# codec_AD1938.net
KiCad netlist of a schematic drawn in EAGLE
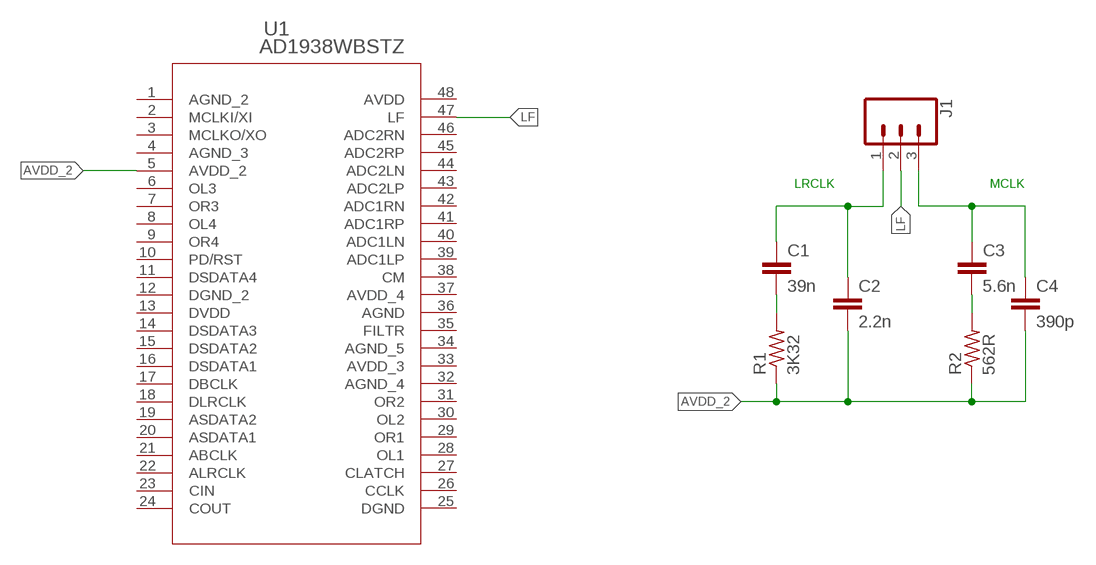
[diagram p0: schematic, sheet 1]
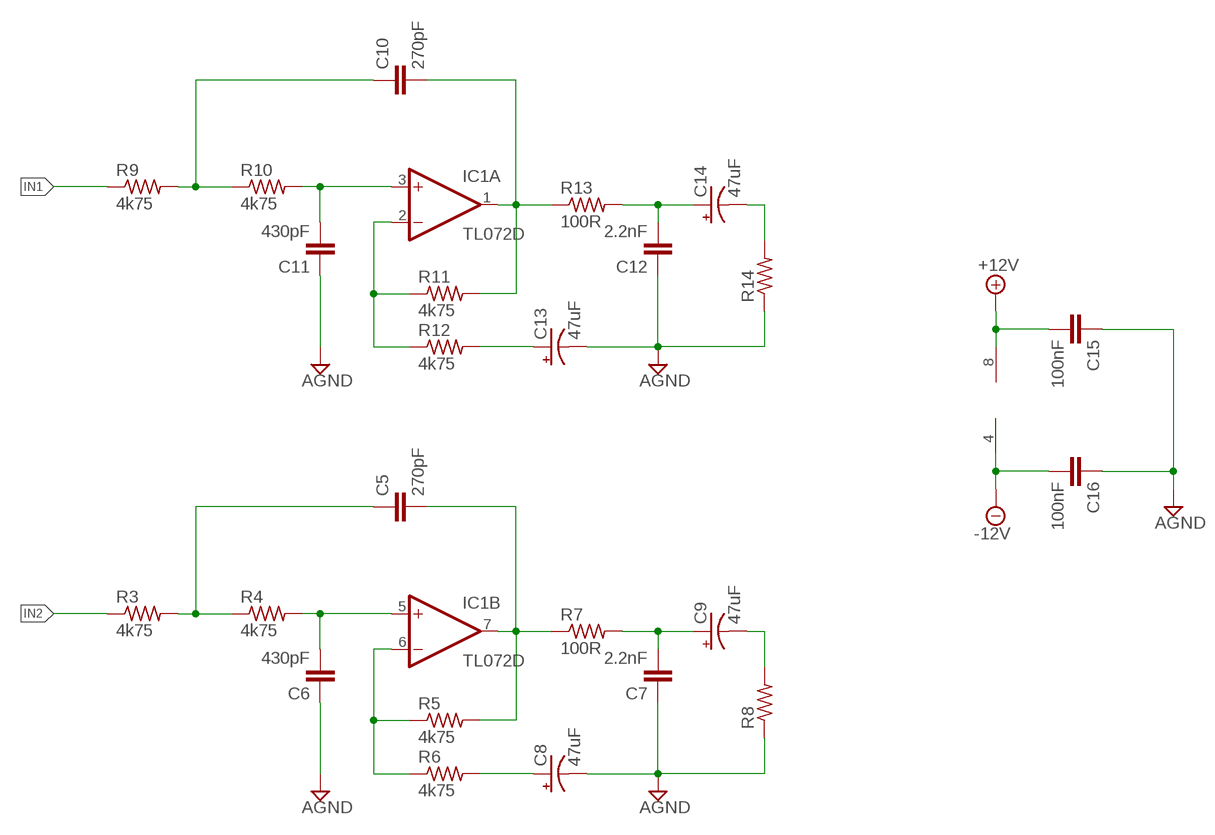
[diagram p1: schematic, sheet 2]

(export (version "E")
  (design (tool "Eeschema 10.0.6"))
  (components
    (comp (ref "C5")
      (value "270pF")
      (footprint "eagle-import:C0603")
      (libsource (lib "eagle-import") (part "C-EUC0603"))
    )
    (comp (ref "C6")
      (value "430pF")
      (footprint "eagle-import:C0603")
      (libsource (lib "eagle-import") (part "C-EUC0603"))
    )
    (comp (ref "C7")
      (value "2.2nF")
      (footprint "eagle-import:C0603")
      (libsource (lib "eagle-import") (part "C-EUC0603"))
    )
    (comp (ref "C8")
      (value "47uF")
      (footprint "eagle-import:UD-5X5,8_NICHICON")
      (libsource (lib "eagle-import") (part "CPOL-USUD-5X5,8"))
    )
    (comp (ref "C9")
      (value "47uF")
      (footprint "eagle-import:UD-5X5,8_NICHICON")
      (libsource (lib "eagle-import") (part "CPOL-USUD-5X5,8"))
    )
    (comp (ref "C10")
      (value "270pF")
      (footprint "eagle-import:C0603")
      (libsource (lib "eagle-import") (part "C-EUC0603"))
    )
    (comp (ref "C11")
      (value "430pF")
      (footprint "eagle-import:C0603")
      (libsource (lib "eagle-import") (part "C-EUC0603"))
    )
    (comp (ref "C12")
      (value "2.2nF")
      (footprint "eagle-import:C0603")
      (libsource (lib "eagle-import") (part "C-EUC0603"))
    )
    (comp (ref "C13")
      (value "47uF")
      (footprint "eagle-import:UD-5X5,8_NICHICON")
      (libsource (lib "eagle-import") (part "CPOL-USUD-5X5,8"))
    )
    (comp (ref "C14")
      (value "47uF")
      (footprint "eagle-import:UD-5X5,8_NICHICON")
      (libsource (lib "eagle-import") (part "CPOL-USUD-5X5,8"))
    )
    (comp (ref "C15")
      (value "100nF")
      (footprint "eagle-import:C0603")
      (libsource (lib "eagle-import") (part "C-EUC0603"))
    )
    (comp (ref "C16")
      (value "100nF")
      (footprint "eagle-import:C0603")
      (libsource (lib "eagle-import") (part "C-EUC0603"))
    )
    (comp (ref "IC1")
      (value "TL072D")
      (footprint "eagle-import:SO08")
      (libsource (lib "eagle-import") (part "TL072D"))
    )
    (comp (ref "R3")
      (value "4k75")
      (footprint "eagle-import:R0603")
      (libsource (lib "eagle-import") (part "R-US_R0603"))
    )
    (comp (ref "R4")
      (value "4k75")
      (footprint "eagle-import:R0603")
      (libsource (lib "eagle-import") (part "R-US_R0603"))
    )
    (comp (ref "R5")
      (value "4k75")
      (footprint "eagle-import:R0603")
      (libsource (lib "eagle-import") (part "R-US_R0603"))
    )
    (comp (ref "R6")
      (value "4k75")
      (footprint "eagle-import:R0603")
      (libsource (lib "eagle-import") (part "R-US_R0603"))
    )
    (comp (ref "R7")
      (value "100R")
      (footprint "eagle-import:R0603")
      (libsource (lib "eagle-import") (part "R-US_R0603"))
    )
    (comp (ref "R8")
      (value "R-US_R0603")
      (footprint "eagle-import:R0603")
      (libsource (lib "eagle-import") (part "R-US_R0603"))
    )
    (comp (ref "R9")
      (value "4k75")
      (footprint "eagle-import:R0603")
      (libsource (lib "eagle-import") (part "R-US_R0603"))
    )
    (comp (ref "R10")
      (value "4k75")
      (footprint "eagle-import:R0603")
      (libsource (lib "eagle-import") (part "R-US_R0603"))
    )
    (comp (ref "R11")
      (value "4k75")
      (footprint "eagle-import:R0603")
      (libsource (lib "eagle-import") (part "R-US_R0603"))
    )
    (comp (ref "R12")
      (value "4k75")
      (footprint "eagle-import:R0603")
      (libsource (lib "eagle-import") (part "R-US_R0603"))
    )
    (comp (ref "R13")
      (value "100R")
      (footprint "eagle-import:R0603")
      (libsource (lib "eagle-import") (part "R-US_R0603"))
    )
    (comp (ref "R14")
      (value "R-US_R0603")
      (footprint "eagle-import:R0603")
      (libsource (lib "eagle-import") (part "R-US_R0603"))
    )
    (comp (ref "C1")
      (value "39n")
      (footprint "eagle-import:C0603")
      (libsource (lib "eagle-import") (part "C-EUC0603"))
    )
    (comp (ref "C2")
      (value "2.2n")
      (footprint "eagle-import:C0603")
      (libsource (lib "eagle-import") (part "C-EUC0603"))
    )
    (comp (ref "C3")
      (value "5.6n")
      (footprint "eagle-import:C0603")
      (libsource (lib "eagle-import") (part "C-EUC0603"))
    )
    (comp (ref "C4")
      (value "390p")
      (footprint "eagle-import:C0603")
      (libsource (lib "eagle-import") (part "C-EUC0603"))
    )
    (comp (ref "J1")
      (value "CONN_03LOCK_LONGPADS")
      (footprint "eagle-import:1X03_LOCK_LONGPADS")
      (libsource (lib "eagle-import") (part "CONN_03LOCK_LONGPADS"))
    )
    (comp (ref "R1")
      (value "3K32")
      (footprint "eagle-import:R0603")
      (libsource (lib "eagle-import") (part "R-US_R0603"))
    )
    (comp (ref "R2")
      (value "562R")
      (footprint "eagle-import:R0603")
      (libsource (lib "eagle-import") (part "R-US_R0603"))
    )
    (comp (ref "U1")
      (value "AD1938WBSTZ")
      (footprint "eagle-import:ST_48_ADI")
      (fields (field (name "COPYRIGHT") "Copyright (C) 2022 Ultra Librarian. All rights reserved."))
      (libsource (lib "eagle-import") (part "AD1938WBSTZ"))
    )
  )
  (nets
    (net (code "1") (name "+12V") (class "Default")
      (node (ref "C15") (pin "2") (pinfunction "2_2") (pintype "passive"))
      (node (ref "IC1") (pin "8") (pinfunction "V+_8") (pintype "power_in"))
    )
    (net (code "2") (name "-12V") (class "Default")
      (node (ref "C16") (pin "2") (pinfunction "2_2") (pintype "passive"))
      (node (ref "IC1") (pin "4") (pinfunction "V-_4") (pintype "power_in"))
    )
    (net (code "3") (name "AGND") (class "Default")
      (node (ref "C11") (pin "1") (pinfunction "1_1") (pintype "passive"))
      (node (ref "C12") (pin "1") (pinfunction "1_1") (pintype "passive"))
      (node (ref "C13") (pin "-") (pinfunction "-_-") (pintype "passive"))
      (node (ref "C15") (pin "1") (pinfunction "1_1") (pintype "passive"))
      (node (ref "C16") (pin "1") (pinfunction "1_1") (pintype "passive"))
      (node (ref "C6") (pin "1") (pinfunction "1_1") (pintype "passive"))
      (node (ref "C7") (pin "1") (pinfunction "1_1") (pintype "passive"))
      (node (ref "C8") (pin "-") (pinfunction "-_-") (pintype "passive"))
      (node (ref "R14") (pin "1") (pinfunction "1_1") (pintype "passive"))
      (node (ref "R8") (pin "1") (pinfunction "1_1") (pintype "passive"))
    )
    (net (code "4") (name "AVDD") (class "Default")
      (node (ref "U1") (pin "48") (pinfunction "AVDD_48") (pintype "power_in"))
    )
    (net (code "5") (name "AVDD_2") (class "Default")
      (node (ref "C2") (pin "2") (pinfunction "2_2") (pintype "passive"))
      (node (ref "C4") (pin "2") (pinfunction "2_2") (pintype "passive"))
      (node (ref "R1") (pin "1") (pinfunction "1_1") (pintype "passive"))
      (node (ref "R2") (pin "1") (pinfunction "1_1") (pintype "passive"))
      (node (ref "U1") (pin "5") (pinfunction "AVDD_2_5") (pintype "power_in"))
    )
    (net (code "6") (name "AVDD_3") (class "Default")
      (node (ref "U1") (pin "33") (pinfunction "AVDD_3_33") (pintype "power_in"))
    )
    (net (code "7") (name "AVDD_4") (class "Default")
      (node (ref "U1") (pin "37") (pinfunction "AVDD_4_37") (pintype "power_in"))
    )
    (net (code "8") (name "DVDD") (class "Default")
      (node (ref "U1") (pin "13") (pinfunction "DVDD_13") (pintype "power_in"))
    )
    (net (code "9") (name "IN1") (class "Default")
      (node (ref "R9") (pin "1") (pinfunction "1_1") (pintype "passive"))
    )
    (net (code "10") (name "IN2") (class "Default")
      (node (ref "R3") (pin "1") (pinfunction "1_1") (pintype "passive"))
    )
    (net (code "11") (name "LF") (class "Default")
      (node (ref "C1") (pin "1") (pinfunction "1_1") (pintype "passive"))
      (node (ref "C2") (pin "1") (pinfunction "1_1") (pintype "passive"))
      (node (ref "C3") (pin "1") (pinfunction "1_1") (pintype "passive"))
      (node (ref "C4") (pin "1") (pinfunction "1_1") (pintype "passive"))
      (node (ref "J1") (pin "1") (pinfunction "1_1") (pintype "passive"))
      (node (ref "J1") (pin "2") (pinfunction "2_2") (pintype "passive"))
      (node (ref "J1") (pin "3") (pinfunction "3_3") (pintype "passive"))
      (node (ref "U1") (pin "47") (pinfunction "LF_47") (pintype "passive"))
    )
    (net (code "12") (name "Net-(C1-Pad2)") (class "Default")
      (node (ref "C1") (pin "2") (pinfunction "2_2") (pintype "passive"))
      (node (ref "R1") (pin "2") (pinfunction "2_2") (pintype "passive"))
    )
    (net (code "13") (name "Net-(C3-Pad2)") (class "Default")
      (node (ref "C3") (pin "2") (pinfunction "2_2") (pintype "passive"))
      (node (ref "R2") (pin "2") (pinfunction "2_2") (pintype "passive"))
    )
    (net (code "14") (name "Net-(C5-Pad1)") (class "Default")
      (node (ref "C5") (pin "1") (pinfunction "1_1") (pintype "passive"))
      (node (ref "R3") (pin "2") (pinfunction "2_2") (pintype "passive"))
      (node (ref "R4") (pin "1") (pinfunction "1_1") (pintype "passive"))
    )
    (net (code "15") (name "Net-(C7-Pad2)") (class "Default")
      (node (ref "C7") (pin "2") (pinfunction "2_2") (pintype "passive"))
      (node (ref "C9") (pin "+") (pinfunction "+_+") (pintype "passive"))
      (node (ref "R7") (pin "2") (pinfunction "2_2") (pintype "passive"))
    )
    (net (code "16") (name "Net-(C8-Pad+)") (class "Default")
      (node (ref "C8") (pin "+") (pinfunction "+_+") (pintype "passive"))
      (node (ref "R6") (pin "2") (pinfunction "2_2") (pintype "passive"))
    )
    (net (code "17") (name "Net-(C9-Pad-)") (class "Default")
      (node (ref "C9") (pin "-") (pinfunction "-_-") (pintype "passive"))
      (node (ref "R8") (pin "2") (pinfunction "2_2") (pintype "passive"))
    )
    (net (code "18") (name "Net-(C10-Pad1)") (class "Default")
      (node (ref "C10") (pin "1") (pinfunction "1_1") (pintype "passive"))
      (node (ref "R10") (pin "1") (pinfunction "1_1") (pintype "passive"))
      (node (ref "R9") (pin "2") (pinfunction "2_2") (pintype "passive"))
    )
    (net (code "19") (name "Net-(C12-Pad2)") (class "Default")
      (node (ref "C12") (pin "2") (pinfunction "2_2") (pintype "passive"))
      (node (ref "C14") (pin "+") (pinfunction "+_+") (pintype "passive"))
      (node (ref "R13") (pin "2") (pinfunction "2_2") (pintype "passive"))
    )
    (net (code "20") (name "Net-(C13-Pad+)") (class "Default")
      (node (ref "C13") (pin "+") (pinfunction "+_+") (pintype "passive"))
      (node (ref "R12") (pin "2") (pinfunction "2_2") (pintype "passive"))
    )
    (net (code "21") (name "Net-(C14-Pad-)") (class "Default")
      (node (ref "C14") (pin "-") (pinfunction "-_-") (pintype "passive"))
      (node (ref "R14") (pin "2") (pinfunction "2_2") (pintype "passive"))
    )
    (net (code "22") (name "Net-(IC1A-+IN)") (class "Default")
      (node (ref "C11") (pin "2") (pinfunction "2_2") (pintype "passive"))
      (node (ref "IC1") (pin "3") (pinfunction "+IN_3") (pintype "input"))
      (node (ref "R10") (pin "2") (pinfunction "2_2") (pintype "passive"))
    )
    (net (code "23") (name "Net-(IC1A--IN)") (class "Default")
      (node (ref "IC1") (pin "2") (pinfunction "-IN_2") (pintype "input"))
      (node (ref "R11") (pin "1") (pinfunction "1_1") (pintype "passive"))
      (node (ref "R12") (pin "1") (pinfunction "1_1") (pintype "passive"))
    )
    (net (code "24") (name "Net-(IC1A-OUT)") (class "Default")
      (node (ref "C10") (pin "2") (pinfunction "2_2") (pintype "passive"))
      (node (ref "IC1") (pin "1") (pinfunction "OUT_1") (pintype "output"))
      (node (ref "R11") (pin "2") (pinfunction "2_2") (pintype "passive"))
      (node (ref "R13") (pin "1") (pinfunction "1_1") (pintype "passive"))
    )
    (net (code "25") (name "Net-(IC1B-+IN)") (class "Default")
      (node (ref "C6") (pin "2") (pinfunction "2_2") (pintype "passive"))
      (node (ref "IC1") (pin "5") (pinfunction "+IN_5") (pintype "input"))
      (node (ref "R4") (pin "2") (pinfunction "2_2") (pintype "passive"))
    )
    (net (code "26") (name "Net-(IC1B--IN)") (class "Default")
      (node (ref "IC1") (pin "6") (pinfunction "-IN_6") (pintype "input"))
      (node (ref "R5") (pin "1") (pinfunction "1_1") (pintype "passive"))
      (node (ref "R6") (pin "1") (pinfunction "1_1") (pintype "passive"))
    )
    (net (code "27") (name "Net-(IC1B-OUT)") (class "Default")
      (node (ref "C5") (pin "2") (pinfunction "2_2") (pintype "passive"))
      (node (ref "IC1") (pin "7") (pinfunction "OUT_7") (pintype "output"))
      (node (ref "R5") (pin "2") (pinfunction "2_2") (pintype "passive"))
      (node (ref "R7") (pin "1") (pinfunction "1_1") (pintype "passive"))
    )
    (net (code "28") (name "unconnected-(U1-ABCLK-Pad21)") (class "Default")
      (node (ref "U1") (pin "21") (pinfunction "ABCLK_21") (pintype "input"))
    )
    (net (code "29") (name "unconnected-(U1-ADC1LN-Pad40)") (class "Default")
      (node (ref "U1") (pin "40") (pinfunction "ADC1LN_40") (pintype "passive"))
    )
    (net (code "30") (name "unconnected-(U1-ADC1LP-Pad39)") (class "Default")
      (node (ref "U1") (pin "39") (pinfunction "ADC1LP_39") (pintype "passive"))
    )
    (net (code "31") (name "unconnected-(U1-ADC1RN-Pad42)") (class "Default")
      (node (ref "U1") (pin "42") (pinfunction "ADC1RN_42") (pintype "passive"))
    )
    (net (code "32") (name "unconnected-(U1-ADC1RP-Pad41)") (class "Default")
      (node (ref "U1") (pin "41") (pinfunction "ADC1RP_41") (pintype "passive"))
    )
    (net (code "33") (name "unconnected-(U1-ADC2LN-Pad44)") (class "Default")
      (node (ref "U1") (pin "44") (pinfunction "ADC2LN_44") (pintype "passive"))
    )
    (net (code "34") (name "unconnected-(U1-ADC2LP-Pad43)") (class "Default")
      (node (ref "U1") (pin "43") (pinfunction "ADC2LP_43") (pintype "passive"))
    )
    (net (code "35") (name "unconnected-(U1-ADC2RN-Pad46)") (class "Default")
      (node (ref "U1") (pin "46") (pinfunction "ADC2RN_46") (pintype "passive"))
    )
    (net (code "36") (name "unconnected-(U1-ADC2RP-Pad45)") (class "Default")
      (node (ref "U1") (pin "45") (pinfunction "ADC2RP_45") (pintype "passive"))
    )
    (net (code "37") (name "unconnected-(U1-AGND-Pad36)") (class "Default")
      (node (ref "U1") (pin "36") (pinfunction "AGND_36") (pintype "passive"))
    )
    (net (code "38") (name "unconnected-(U1-AGND_2-Pad1)") (class "Default")
      (node (ref "U1") (pin "1") (pinfunction "AGND_2_1") (pintype "passive"))
    )
    (net (code "39") (name "unconnected-(U1-AGND_3-Pad4)") (class "Default")
      (node (ref "U1") (pin "4") (pinfunction "AGND_3_4") (pintype "passive"))
    )
    (net (code "40") (name "unconnected-(U1-AGND_4-Pad32)") (class "Default")
      (node (ref "U1") (pin "32") (pinfunction "AGND_4_32") (pintype "passive"))
    )
    (net (code "41") (name "unconnected-(U1-AGND_5-Pad34)") (class "Default")
      (node (ref "U1") (pin "34") (pinfunction "AGND_5_34") (pintype "passive"))
    )
    (net (code "42") (name "unconnected-(U1-ALRCLK-Pad22)") (class "Default")
      (node (ref "U1") (pin "22") (pinfunction "ALRCLK_22") (pintype "input"))
    )
    (net (code "43") (name "unconnected-(U1-ASDATA1-Pad20)") (class "Default")
      (node (ref "U1") (pin "20") (pinfunction "ASDATA1_20") (pintype "output"))
    )
    (net (code "44") (name "unconnected-(U1-ASDATA2-Pad19)") (class "Default")
      (node (ref "U1") (pin "19") (pinfunction "ASDATA2_19") (pintype "output"))
    )
    (net (code "45") (name "unconnected-(U1-CCLK-Pad26)") (class "Default")
      (node (ref "U1") (pin "26") (pinfunction "CCLK_26") (pintype "input"))
    )
    (net (code "46") (name "unconnected-(U1-CIN-Pad23)") (class "Default")
      (node (ref "U1") (pin "23") (pinfunction "CIN_23") (pintype "input"))
    )
    (net (code "47") (name "unconnected-(U1-CLATCH-Pad27)") (class "Default")
      (node (ref "U1") (pin "27") (pinfunction "CLATCH_27") (pintype "passive"))
    )
    (net (code "48") (name "unconnected-(U1-CM-Pad38)") (class "Default")
      (node (ref "U1") (pin "38") (pinfunction "CM_38") (pintype "passive"))
    )
    (net (code "49") (name "unconnected-(U1-COUT-Pad24)") (class "Default")
      (node (ref "U1") (pin "24") (pinfunction "COUT_24") (pintype "output"))
    )
    (net (code "50") (name "unconnected-(U1-DBCLK-Pad17)") (class "Default")
      (node (ref "U1") (pin "17") (pinfunction "DBCLK_17") (pintype "input"))
    )
    (net (code "51") (name "unconnected-(U1-DGND-Pad25)") (class "Default")
      (node (ref "U1") (pin "25") (pinfunction "DGND_25") (pintype "passive"))
    )
    (net (code "52") (name "unconnected-(U1-DGND_2-Pad12)") (class "Default")
      (node (ref "U1") (pin "12") (pinfunction "DGND_2_12") (pintype "passive"))
    )
    (net (code "53") (name "unconnected-(U1-DLRCLK-Pad18)") (class "Default")
      (node (ref "U1") (pin "18") (pinfunction "DLRCLK_18") (pintype "input"))
    )
    (net (code "54") (name "unconnected-(U1-DSDATA1-Pad16)") (class "Default")
      (node (ref "U1") (pin "16") (pinfunction "DSDATA1_16") (pintype "input"))
    )
    (net (code "55") (name "unconnected-(U1-DSDATA2-Pad15)") (class "Default")
      (node (ref "U1") (pin "15") (pinfunction "DSDATA2_15") (pintype "input"))
    )
    (net (code "56") (name "unconnected-(U1-DSDATA3-Pad14)") (class "Default")
      (node (ref "U1") (pin "14") (pinfunction "DSDATA3_14") (pintype "input"))
    )
    (net (code "57") (name "unconnected-(U1-DSDATA4-Pad11)") (class "Default")
      (node (ref "U1") (pin "11") (pinfunction "DSDATA4_11") (pintype "bidirectional"))
    )
    (net (code "58") (name "unconnected-(U1-FILTR-Pad35)") (class "Default")
      (node (ref "U1") (pin "35") (pinfunction "FILTR_35") (pintype "passive"))
    )
    (net (code "59") (name "unconnected-(U1-MCLKI{slash}XI-Pad2)") (class "Default")
      (node (ref "U1") (pin "2") (pinfunction "MCLKI/XI_2") (pintype "input"))
    )
    (net (code "60") (name "unconnected-(U1-MCLKO{slash}XO-Pad3)") (class "Default")
      (node (ref "U1") (pin "3") (pinfunction "MCLKO/XO_3") (pintype "input"))
    )
    (net (code "61") (name "unconnected-(U1-OL1-Pad28)") (class "Default")
      (node (ref "U1") (pin "28") (pinfunction "OL1_28") (pintype "output"))
    )
    (net (code "62") (name "unconnected-(U1-OL2-Pad30)") (class "Default")
      (node (ref "U1") (pin "30") (pinfunction "OL2_30") (pintype "output"))
    )
    (net (code "63") (name "unconnected-(U1-OL3-Pad6)") (class "Default")
      (node (ref "U1") (pin "6") (pinfunction "OL3_6") (pintype "output"))
    )
    (net (code "64") (name "unconnected-(U1-OL4-Pad8)") (class "Default")
      (node (ref "U1") (pin "8") (pinfunction "OL4_8") (pintype "output"))
    )
    (net (code "65") (name "unconnected-(U1-OR1-Pad29)") (class "Default")
      (node (ref "U1") (pin "29") (pinfunction "OR1_29") (pintype "output"))
    )
    (net (code "66") (name "unconnected-(U1-OR2-Pad31)") (class "Default")
      (node (ref "U1") (pin "31") (pinfunction "OR2_31") (pintype "output"))
    )
    (net (code "67") (name "unconnected-(U1-OR3-Pad7)") (class "Default")
      (node (ref "U1") (pin "7") (pinfunction "OR3_7") (pintype "output"))
    )
    (net (code "68") (name "unconnected-(U1-OR4-Pad9)") (class "Default")
      (node (ref "U1") (pin "9") (pinfunction "OR4_9") (pintype "output"))
    )
    (net (code "69") (name "unconnected-(U1-PD{slash}RST-Pad10)") (class "Default")
      (node (ref "U1") (pin "10") (pinfunction "PD/RST_10") (pintype "passive"))
    )
  )
)
